# USB_OTG_HS_PHY.net
KiCad netlist of a schematic drawn in Altium Designer
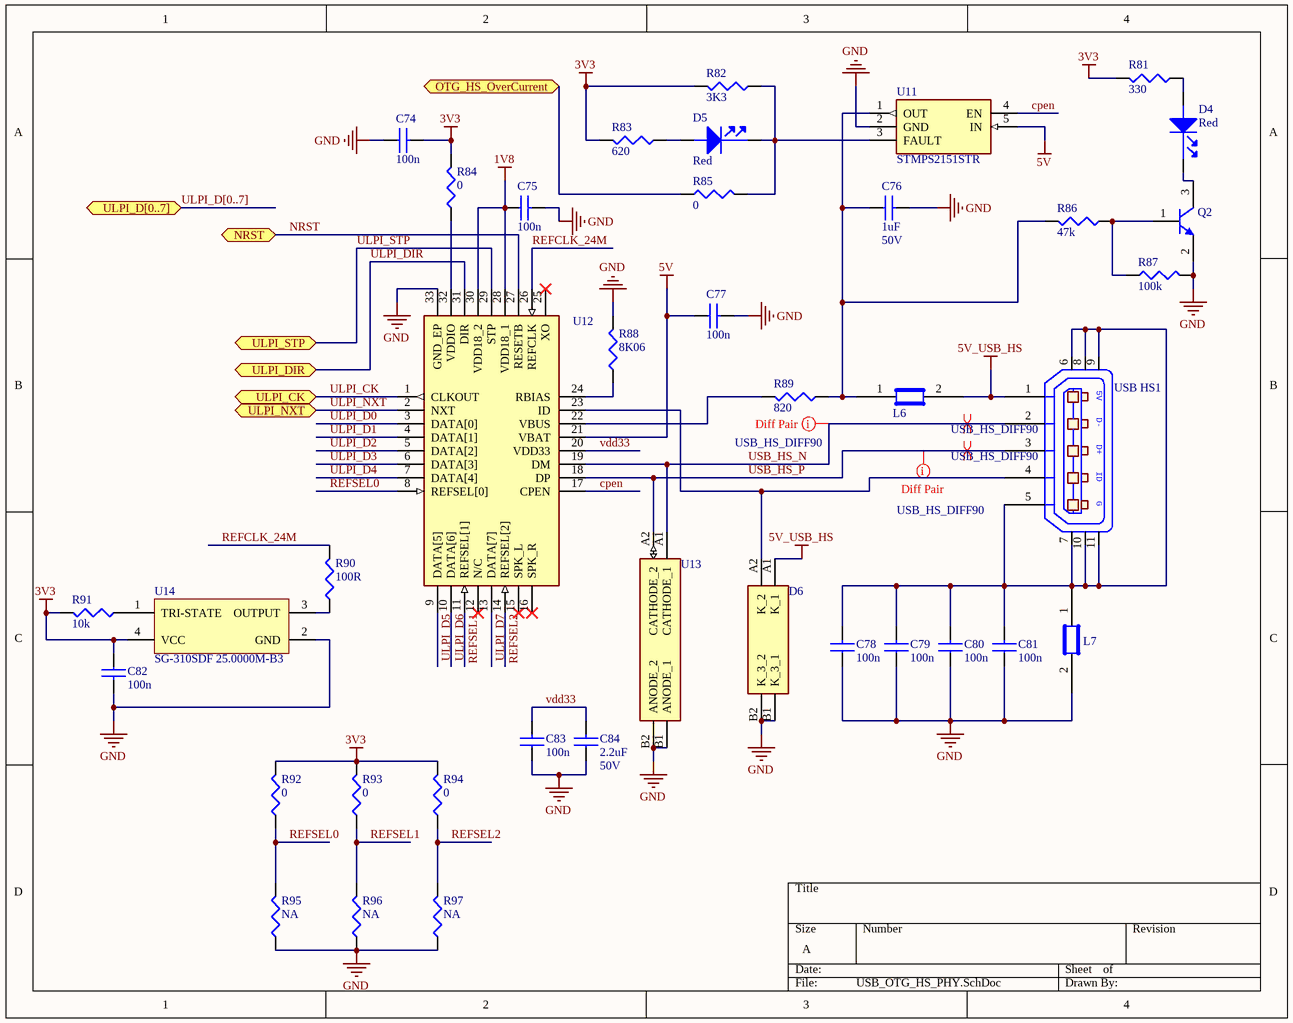
[diagram p0: USB_OTG_HS_PHY.SchDoc]

(export (version "E")
  (design (tool "Eeschema 10.0.6"))
  (components
    (comp (ref "C74")
      (value "100n")
      (footprint "C0402")
      (description "CAP CER .10UF 50V X5R 10% 0402")
      (fields
        (field (name "MANUFACTURER") "TDK Corporation")
        (field (name "MANUFACTURER PART NUMBER") "C1005X5R1H104K")
      )
      (libsource (lib "iMX6_Rex_Development_Baseboard_V1I1") (part "C1005X5R1H104K"))
    )
    (comp (ref "C75")
      (value "100n")
      (footprint "C0402")
      (description "CAP CER .10UF 50V X5R 10% 0402")
      (fields
        (field (name "MANUFACTURER") "TDK Corporation")
        (field (name "MANUFACTURER PART NUMBER") "C1005X5R1H104K")
      )
      (libsource (lib "iMX6_Rex_Development_Baseboard_V1I1") (part "C1005X5R1H104K"))
    )
    (comp (ref "C76")
      (value "1uF")
      (footprint "C0805")
      (description "CAP CER 1UF 50V X7R 0805")
      (fields
        (field (name "MANUFACTURER") "Murata Electronics North America")
        (field (name "MANUFACTURER PART NUMBER") "GRM21BR71H105KA12L")
        (field (name "VOLTAGE - RATED") "50V")
      )
      (libsource (lib "iMX6_Rex_Development_Baseboard_V1I1") (part "GRM21BR71H105KA12L"))
    )
    (comp (ref "C77")
      (value "100n")
      (footprint "C0402")
      (description "CAP CER .10UF 50V X5R 10% 0402")
      (fields
        (field (name "MANUFACTURER") "TDK Corporation")
        (field (name "MANUFACTURER PART NUMBER") "C1005X5R1H104K")
      )
      (libsource (lib "iMX6_Rex_Development_Baseboard_V1I1") (part "C1005X5R1H104K"))
    )
    (comp (ref "C78")
      (value "100n")
      (footprint "C0402")
      (description "CAP CER .10UF 50V X5R 10% 0402")
      (fields
        (field (name "MANUFACTURER") "TDK Corporation")
        (field (name "MANUFACTURER PART NUMBER") "C1005X5R1H104K")
      )
      (libsource (lib "iMX6_Rex_Development_Baseboard_V1I1") (part "C1005X5R1H104K"))
    )
    (comp (ref "C79")
      (value "100n")
      (footprint "C0402")
      (description "CAP CER .10UF 50V X5R 10% 0402")
      (fields
        (field (name "MANUFACTURER") "TDK Corporation")
        (field (name "MANUFACTURER PART NUMBER") "C1005X5R1H104K")
      )
      (libsource (lib "iMX6_Rex_Development_Baseboard_V1I1") (part "C1005X5R1H104K"))
    )
    (comp (ref "C80")
      (value "100n")
      (footprint "C0402")
      (description "CAP CER .10UF 50V X5R 10% 0402")
      (fields
        (field (name "MANUFACTURER") "TDK Corporation")
        (field (name "MANUFACTURER PART NUMBER") "C1005X5R1H104K")
      )
      (libsource (lib "iMX6_Rex_Development_Baseboard_V1I1") (part "C1005X5R1H104K"))
    )
    (comp (ref "C81")
      (value "100n")
      (footprint "C0402")
      (description "CAP CER .10UF 50V X5R 10% 0402")
      (fields
        (field (name "MANUFACTURER") "TDK Corporation")
        (field (name "MANUFACTURER PART NUMBER") "C1005X5R1H104K")
      )
      (libsource (lib "iMX6_Rex_Development_Baseboard_V1I1") (part "C1005X5R1H104K"))
    )
    (comp (ref "C82")
      (value "100n")
      (footprint "C0402")
      (description "CAP CER .10UF 50V X5R 10% 0402")
      (fields
        (field (name "MANUFACTURER") "TDK Corporation")
        (field (name "MANUFACTURER PART NUMBER") "C1005X5R1H104K")
      )
      (libsource (lib "iMX6_Rex_Development_Baseboard_V1I1") (part "C1005X5R1H104K"))
    )
    (comp (ref "C83")
      (value "100n")
      (footprint "C0402")
      (description "CAP CER .10UF 50V X5R 10% 0402")
      (fields
        (field (name "MANUFACTURER") "TDK Corporation")
        (field (name "MANUFACTURER PART NUMBER") "C1005X5R1H104K")
      )
      (libsource (lib "iMX6_Rex_Development_Baseboard_V1I1") (part "C1005X5R1H104K"))
    )
    (comp (ref "C84")
      (value "2.2uF")
      (footprint "C0805")
      (description "CAP CER 1UF 50V X7R 0805")
      (fields
        (field (name "MANUFACTURER") "Murata Electronics North America")
        (field (name "MANUFACTURER PART NUMBER") "GRM21BR71H105KA12L")
        (field (name "VOLTAGE - RATED") "50V")
      )
      (libsource (lib "iMX6_Rex_Development_Baseboard_V1I1") (part "GRM21BR71H105KA12L"))
    )
    (comp (ref "D4")
      (value "Red")
      (footprint "LED_0603")
      (description "LED SMARTLED RED 630NM 0603 SMD")
      (fields
        (field (name "MANUFACTURER") "OSRAM Opto Semiconductors Inc")
        (field (name "MANUFACTURER PART NUMBER") "LS L29K-H1J2-1-Z")
        (field (name ".CHECKED PCB") "RF")
        (field (name ".CHECKED SCH") "RF")
      )
      (libsource (lib "iMX6_Rex_Development_Baseboard_V1I1") (part "LS L29K-H1J2-1-Z"))
    )
    (comp (ref "D5")
      (value "Red")
      (footprint "LED_0603")
      (description "LED SMARTLED RED 630NM 0603 SMD")
      (fields
        (field (name "MANUFACTURER") "OSRAM Opto Semiconductors Inc")
        (field (name "MANUFACTURER PART NUMBER") "LS L29K-H1J2-1-Z")
        (field (name ".CHECKED PCB") "RF")
        (field (name ".CHECKED SCH") "RF")
      )
      (libsource (lib "iMX6_Rex_Development_Baseboard_V1I1") (part "LS L29K-H1J2-1-Z"))
    )
    (comp (ref "D6")
      (value "ESDA14V2-2BF3")
      (footprint "SamacSys:BGA4C40P2X2_77X77X66")
      (description "TVS Diode (Bi-directional)")
      (fields (field (name "MOUSER PART NUMBER") "511-ESDA14V2-2BF3"))
      (libsource (lib "*") (part "ESDA14V2-2BF3"))
    )
    (comp (ref "L6")
      (value "MPZ1608S601A 600OHM/1A")
      (footprint "C0603")
      (description "FERRITE CHIP BEAD 600 OHM SMD 1A")
      (fields
        (field (name "MANUFACTURER") "TDK Corporation")
        (field (name "MANUFACTURER PART NUMBER") "MPZ1608S601A")
        (field (name ".CHECKED PCB") "RF")
        (field (name ".CHECKED SCH") "RF")
      )
      (libsource (lib "iMX6_Rex_Development_Baseboard_V1I1") (part "MPZ1608S601A"))
    )
    (comp (ref "L7")
      (value "MPZ1608S601A 600OHM/1A")
      (footprint "C0603")
      (description "FERRITE CHIP BEAD 600 OHM SMD 1A")
      (fields
        (field (name "MANUFACTURER") "TDK Corporation")
        (field (name "MANUFACTURER PART NUMBER") "MPZ1608S601A")
        (field (name ".CHECKED PCB") "RF")
        (field (name ".CHECKED SCH") "RF")
      )
      (libsource (lib "iMX6_Rex_Development_Baseboard_V1I1") (part "MPZ1608S601A"))
    )
    (comp (ref "Q2")
      (value "MMBT2222A-7-F")
      (footprint "DIOD-SOT23-3_V")
      (description "NPN Small Signal Transistor, 40 V, -55 to 150 degC, 3-Pin SOT23, RoHS, Tape and Reel")
      (fields (field (name "MANUFACTURER") "Diodes Inc"))
      (libsource (lib "MiniPC") (part "CMP-1693-00003-1"))
    )
    (comp (ref "R81")
      (value "330")
      (footprint "R0402")
      (description "RES 10.0K OHM 1/16W 1% 0402 SMD")
      (fields
        (field (name "MANUFACTURER") "Yageo")
        (field (name "MANUFACTURER PART NUMBER") "RC0402FR-0710KL")
      )
      (libsource (lib "iMX6_Rex_Development_Baseboard_V1I1") (part "RC0402FR-0710KL"))
    )
    (comp (ref "R82")
      (value "3K3")
      (footprint "R0402")
      (description "RES 10.0K OHM 1/16W 1% 0402 SMD")
      (fields
        (field (name "MANUFACTURER") "Yageo")
        (field (name "MANUFACTURER PART NUMBER") "RC0402FR-0710KL")
      )
      (libsource (lib "iMX6_Rex_Development_Baseboard_V1I1") (part "RC0402FR-0710KL"))
    )
    (comp (ref "R83")
      (value "620")
      (footprint "R0402")
      (description "RES 10.0K OHM 1/16W 1% 0402 SMD")
      (fields
        (field (name "MANUFACTURER") "Yageo")
        (field (name "MANUFACTURER PART NUMBER") "RC0402FR-0710KL")
      )
      (libsource (lib "iMX6_Rex_Development_Baseboard_V1I1") (part "RC0402FR-0710KL"))
    )
    (comp (ref "R84")
      (value "0")
      (footprint "R0402")
      (description "RES 100 OHM 1/16W 1% 0402 SMD")
      (fields
        (field (name "MANUFACTURER") "Yageo")
        (field (name "MANUFACTURER PART NUMBER") "RC0402FR-07100RL")
        (field (name ".CHECKED PCB") "RF")
        (field (name ".CHECKED SCH") "RF")
      )
      (libsource (lib "iMX6_Rex_Development_Baseboard_V1I1") (part "RC0402FR-07100RL"))
    )
    (comp (ref "R85")
      (value "0")
      (footprint "R0402")
      (description "RES 100 OHM 1/16W 1% 0402 SMD")
      (fields
        (field (name "MANUFACTURER") "Yageo")
        (field (name "MANUFACTURER PART NUMBER") "RC0402FR-07100RL")
        (field (name ".CHECKED PCB") "RF")
        (field (name ".CHECKED SCH") "RF")
      )
      (libsource (lib "iMX6_Rex_Development_Baseboard_V1I1") (part "RC0402FR-07100RL"))
    )
    (comp (ref "R86")
      (value "47k")
      (footprint "R0402")
      (description "RES 10.0K OHM 1/16W 1% 0402 SMD")
      (fields
        (field (name "MANUFACTURER") "Yageo")
        (field (name "MANUFACTURER PART NUMBER") "RC0402FR-0710KL")
      )
      (libsource (lib "iMX6_Rex_Development_Baseboard_V1I1") (part "RC0402FR-0710KL"))
    )
    (comp (ref "R87")
      (value "100k")
      (footprint "R0402")
      (description "RES 100K OHM 1/16W 1% 0402 SMD")
      (fields
        (field (name "MANUFACTURER") "Stackpole Electronics Inc")
        (field (name "MANUFACTURER PART NUMBER") "RMCF0402FT100K")
      )
      (libsource (lib "iMX6_Rex_Development_Baseboard_V1I1") (part "RMCF0402FT100K"))
    )
    (comp (ref "R88")
      (value "8K06")
      (footprint "R0402")
      (description "RES 10.0K OHM 1/16W 1% 0402 SMD")
      (fields
        (field (name "MANUFACTURER") "Yageo")
        (field (name "MANUFACTURER PART NUMBER") "RC0402FR-0710KL")
      )
      (libsource (lib "iMX6_Rex_Development_Baseboard_V1I1") (part "RC0402FR-0710KL"))
    )
    (comp (ref "R89")
      (value "820")
      (footprint "R0402")
      (description "RES 10.0K OHM 1/16W 1% 0402 SMD")
      (fields
        (field (name "MANUFACTURER") "Yageo")
        (field (name "MANUFACTURER PART NUMBER") "RC0402FR-0710KL")
      )
      (libsource (lib "iMX6_Rex_Development_Baseboard_V1I1") (part "RC0402FR-0710KL"))
    )
    (comp (ref "R90")
      (value "100R")
      (footprint "R0402")
      (description "RES 100 OHM 1/16W 1% 0402 SMD")
      (fields
        (field (name "MANUFACTURER") "Yageo")
        (field (name "MANUFACTURER PART NUMBER") "RC0402FR-07100RL")
        (field (name ".CHECKED PCB") "RF")
        (field (name ".CHECKED SCH") "RF")
      )
      (libsource (lib "iMX6_Rex_Development_Baseboard_V1I1") (part "RC0402FR-07100RL"))
    )
    (comp (ref "R91")
      (value "10k")
      (footprint "R0402")
      (description "RES 10.0K OHM 1/16W 1% 0402 SMD")
      (fields
        (field (name "MANUFACTURER") "Yageo")
        (field (name "MANUFACTURER PART NUMBER") "RC0402FR-0710KL")
      )
      (libsource (lib "iMX6_Rex_Development_Baseboard_V1I1") (part "RC0402FR-0710KL"))
    )
    (comp (ref "R92")
      (value "0")
      (footprint "R0402")
      (description "RES 100 OHM 1/16W 1% 0402 SMD")
      (fields
        (field (name "MANUFACTURER") "Yageo")
        (field (name "MANUFACTURER PART NUMBER") "RC0402FR-07100RL")
        (field (name ".CHECKED PCB") "RF")
        (field (name ".CHECKED SCH") "RF")
      )
      (libsource (lib "iMX6_Rex_Development_Baseboard_V1I1") (part "RC0402FR-07100RL"))
    )
    (comp (ref "R93")
      (value "0")
      (footprint "R0402")
      (description "RES 100 OHM 1/16W 1% 0402 SMD")
      (fields
        (field (name "MANUFACTURER") "Yageo")
        (field (name "MANUFACTURER PART NUMBER") "RC0402FR-07100RL")
        (field (name ".CHECKED PCB") "RF")
        (field (name ".CHECKED SCH") "RF")
      )
      (libsource (lib "iMX6_Rex_Development_Baseboard_V1I1") (part "RC0402FR-07100RL"))
    )
    (comp (ref "R94")
      (value "0")
      (footprint "R0402")
      (description "RES 100 OHM 1/16W 1% 0402 SMD")
      (fields
        (field (name "MANUFACTURER") "Yageo")
        (field (name "MANUFACTURER PART NUMBER") "RC0402FR-07100RL")
        (field (name ".CHECKED PCB") "RF")
        (field (name ".CHECKED SCH") "RF")
      )
      (libsource (lib "iMX6_Rex_Development_Baseboard_V1I1") (part "RC0402FR-07100RL"))
    )
    (comp (ref "R95")
      (value "NA")
      (footprint "R0402")
      (description "RES 100 OHM 1/16W 1% 0402 SMD")
      (fields
        (field (name "MANUFACTURER") "Yageo")
        (field (name "MANUFACTURER PART NUMBER") "RC0402FR-07100RL")
        (field (name ".CHECKED PCB") "RF")
        (field (name ".CHECKED SCH") "RF")
      )
      (libsource (lib "iMX6_Rex_Development_Baseboard_V1I1") (part "RC0402FR-07100RL"))
    )
    (comp (ref "R96")
      (value "NA")
      (footprint "R0402")
      (description "RES 100 OHM 1/16W 1% 0402 SMD")
      (fields
        (field (name "MANUFACTURER") "Yageo")
        (field (name "MANUFACTURER PART NUMBER") "RC0402FR-07100RL")
        (field (name ".CHECKED PCB") "RF")
        (field (name ".CHECKED SCH") "RF")
      )
      (libsource (lib "iMX6_Rex_Development_Baseboard_V1I1") (part "RC0402FR-07100RL"))
    )
    (comp (ref "R97")
      (value "NA")
      (footprint "R0402")
      (description "RES 100 OHM 1/16W 1% 0402 SMD")
      (fields
        (field (name "MANUFACTURER") "Yageo")
        (field (name "MANUFACTURER PART NUMBER") "RC0402FR-07100RL")
        (field (name ".CHECKED PCB") "RF")
        (field (name ".CHECKED SCH") "RF")
      )
      (libsource (lib "iMX6_Rex_Development_Baseboard_V1I1") (part "RC0402FR-07100RL"))
    )
    (comp (ref "U11")
      (value "STMPS2151STR")
      (footprint "SamacSys:SOT95P280X145-5N")
      (description "Integrated Circuit")
      (fields
        (field (name "MOUSER PART NUMBER") "511-STMPS2151STR")
        (field (name "RS PART NUMBER") "8805415P")
      )
      (libsource (lib "*") (part "STMPS2151STR"))
    )
    (comp (ref "U12")
      (value "USB3320C-EZK-TR")
      (footprint "SamacSys:QFN50P500X500X100-33N-D")
      (description "Integrated Circuit")
      (fields
        (field (name "MOUSER PART NUMBER") "886-USB3320C-EZK-TR")
        (field (name "RS PART NUMBER") "8246295P")
      )
      (libsource (lib "*") (part "USB3320C-EZK-TR"))
    )
    (comp (ref "U13")
      (value "USBULC6-2F3")
      (footprint "SamacSys:BGA4C40P2X2_82X82X66")
      (description "Integrated Circuit")
      (fields (field (name "MOUSER PART NUMBER") "511-USBULC6-2F3"))
      (libsource (lib "*") (part "USBULC6-2F3"))
    )
    (comp (ref "U14")
      (value "SG-310SDF 25.0000M-B3")
      (footprint "EPSON-SG-310-4_V")
      (description "Crystal Oscillator (SPXO), 2.5 V, 25 MHz, -20 to 70 degC, 4-Pin SMD, RoHS, Tape and Reel")
      (libsource (lib "MiniPC") (part "CMP-1695-00002-3"))
    )
    (comp (ref "USB HS1")
      (value "USB MICRO AB")
      (footprint "USB_Micro_AB")
      (description "CONN RCPT MICRO USB AB R/A SMD")
      (fields
        (field (name "MANUFACTURER") "Molex Inc")
        (field (name "MANUFACTURER PART NUMBER") "0475890001")
        (field (name ".CREATOR") "MM")
        (field (name ".CHECKED PCB") "MM")
        (field (name ".CHECKED SCH") "MM")
      )
      (libsource (lib "iMX6_Rex_Development_Baseboard_V1I1") (part "0475890001"))
    )
  )
  (nets
    (net (code "1") (name "/NRST") (class "Default")
      (node (ref "U12") (pin "27") (pinfunction "RESETB_27") (pintype "passive"))
    )
    (net (code "2") (name "/OTG_HS_OverCurrent") (class "Default")
      (node (ref "R85") (pin "1") (pinfunction "1_1") (pintype "passive"))
    )
    (net (code "3") (name "/REFCLK_24M") (class "Default")
      (node (ref "R90") (pin "2") (pinfunction "2_2") (pintype "passive"))
      (node (ref "U12") (pin "26") (pinfunction "REFCLK_26") (pintype "input"))
    )
    (net (code "4") (name "/REFSEL0") (class "Default")
      (node (ref "R92") (pin "1") (pinfunction "1_1") (pintype "passive"))
      (node (ref "R95") (pin "2") (pinfunction "2_2") (pintype "passive"))
      (node (ref "U12") (pin "8") (pinfunction "REFSEL[0]_8") (pintype "input"))
    )
    (net (code "5") (name "/REFSEL1") (class "Default")
      (node (ref "R93") (pin "1") (pinfunction "1_1") (pintype "passive"))
      (node (ref "R96") (pin "2") (pinfunction "2_2") (pintype "passive"))
      (node (ref "U12") (pin "11") (pinfunction "REFSEL[1]_11") (pintype "input"))
    )
    (net (code "6") (name "/REFSEL2") (class "Default")
      (node (ref "R94") (pin "1") (pinfunction "1_1") (pintype "passive"))
      (node (ref "R97") (pin "2") (pinfunction "2_2") (pintype "passive"))
      (node (ref "U12") (pin "14") (pinfunction "REFSEL[2]_14") (pintype "input"))
    )
    (net (code "7") (name "/ULPI_CK") (class "Default")
      (node (ref "U12") (pin "1") (pinfunction "CLKOUT_1") (pintype "output"))
    )
    (net (code "8") (name "/ULPI_D0") (class "Default")
      (node (ref "U12") (pin "3") (pinfunction "DATA[0]_3") (pintype "passive"))
    )
    (net (code "9") (name "/ULPI_D1") (class "Default")
      (node (ref "U12") (pin "4") (pinfunction "DATA[1]_4") (pintype "passive"))
    )
    (net (code "10") (name "/ULPI_D2") (class "Default")
      (node (ref "U12") (pin "5") (pinfunction "DATA[2]_5") (pintype "passive"))
    )
    (net (code "11") (name "/ULPI_D3") (class "Default")
      (node (ref "U12") (pin "6") (pinfunction "DATA[3]_6") (pintype "passive"))
    )
    (net (code "12") (name "/ULPI_D4") (class "Default")
      (node (ref "U12") (pin "7") (pinfunction "DATA[4]_7") (pintype "passive"))
    )
    (net (code "13") (name "/ULPI_D5") (class "Default")
      (node (ref "U12") (pin "9") (pinfunction "DATA[5]_9") (pintype "passive"))
    )
    (net (code "14") (name "/ULPI_D6") (class "Default")
      (node (ref "U12") (pin "10") (pinfunction "DATA[6]_10") (pintype "passive"))
    )
    (net (code "15") (name "/ULPI_D7") (class "Default")
      (node (ref "U12") (pin "13") (pinfunction "DATA[7]_13") (pintype "passive"))
    )
    (net (code "16") (name "/ULPI_DIR") (class "Default")
      (node (ref "U12") (pin "31") (pinfunction "DIR_31") (pintype "passive"))
    )
    (net (code "18") (name "/ULPI_NXT") (class "Default")
      (node (ref "U12") (pin "2") (pinfunction "NXT_2") (pintype "passive"))
    )
    (net (code "19") (name "/ULPI_STP") (class "Default")
      (node (ref "U12") (pin "29") (pinfunction "STP_29") (pintype "passive"))
    )
    (net (code "20") (name "/USB_HS_N") (class "Default")
      (node (ref "U12") (pin "19") (pinfunction "DM_19") (pintype "passive"))
      (node (ref "U13") (pin "A1") (pinfunction "CATHODE_1_A1") (pintype "passive"))
      (node (ref "USB HS1") (pin "2") (pinfunction "P2_2") (pintype "passive"))
    )
    (net (code "21") (name "/USB_HS_P") (class "Default")
      (node (ref "U12") (pin "18") (pinfunction "DP_18") (pintype "passive"))
      (node (ref "U13") (pin "A2") (pinfunction "CATHODE_2_A2") (pintype "bidirectional"))
      (node (ref "USB HS1") (pin "3") (pinfunction "P3_3") (pintype "passive"))
    )
    (net (code "22") (name "/cpen") (class "Default")
      (node (ref "U11") (pin "4") (pinfunction "EN_4") (pintype "passive"))
      (node (ref "U12") (pin "17") (pinfunction "CPEN_17") (pintype "passive"))
    )
    (net (code "23") (name "/vdd33") (class "Default")
      (node (ref "C83") (pin "2") (pinfunction "2_2") (pintype "passive"))
      (node (ref "C84") (pin "2") (pinfunction "2_2") (pintype "passive"))
      (node (ref "U12") (pin "20") (pinfunction "VDD33_20") (pintype "power_in"))
    )
    (net (code "24") (name "1V8") (class "Default")
      (node (ref "C75") (pin "1") (pinfunction "1_1") (pintype "passive"))
      (node (ref "U12") (pin "28") (pinfunction "VDD18_1_28") (pintype "power_in"))
      (node (ref "U12") (pin "30") (pinfunction "VDD18_2_30") (pintype "power_in"))
    )
    (net (code "25") (name "3V3") (class "Default")
      (node (ref "C74") (pin "2") (pinfunction "2_2") (pintype "passive"))
      (node (ref "C82") (pin "1") (pinfunction "1_1") (pintype "passive"))
      (node (ref "R81") (pin "2") (pinfunction "2_2") (pintype "passive"))
      (node (ref "R82") (pin "2") (pinfunction "2_2") (pintype "passive"))
      (node (ref "R83") (pin "2") (pinfunction "2_2") (pintype "passive"))
      (node (ref "R84") (pin "2") (pinfunction "2_2") (pintype "passive"))
      (node (ref "R91") (pin "2") (pinfunction "2_2") (pintype "passive"))
      (node (ref "R92") (pin "2") (pinfunction "2_2") (pintype "passive"))
      (node (ref "R93") (pin "2") (pinfunction "2_2") (pintype "passive"))
      (node (ref "R94") (pin "2") (pinfunction "2_2") (pintype "passive"))
      (node (ref "U14") (pin "4") (pinfunction "VCC_4") (pintype "power_in"))
    )
    (net (code "26") (name "5V") (class "Default")
      (node (ref "C77") (pin "1") (pinfunction "1_1") (pintype "passive"))
      (node (ref "U11") (pin "5") (pinfunction "IN_5") (pintype "input"))
      (node (ref "U12") (pin "21") (pinfunction "VBAT_21") (pintype "passive"))
    )
    (net (code "27") (name "5V_USB_HS") (class "Default")
      (node (ref "D6") (pin "A1") (pinfunction "K_1_A1") (pintype "passive"))
      (node (ref "L6") (pin "2") (pinfunction "2_2") (pintype "passive"))
      (node (ref "USB HS1") (pin "1") (pinfunction "P1_1") (pintype "passive"))
    )
    (net (code "28") (name "GND") (class "Default")
      (node (ref "C74") (pin "1") (pinfunction "1_1") (pintype "passive"))
      (node (ref "C75") (pin "2") (pinfunction "2_2") (pintype "passive"))
      (node (ref "C76") (pin "2") (pinfunction "2_2") (pintype "passive"))
      (node (ref "C77") (pin "2") (pinfunction "2_2") (pintype "passive"))
      (node (ref "C78") (pin "1") (pinfunction "1_1") (pintype "passive"))
      (node (ref "C79") (pin "1") (pinfunction "1_1") (pintype "passive"))
      (node (ref "C80") (pin "1") (pinfunction "1_1") (pintype "passive"))
      (node (ref "C81") (pin "1") (pinfunction "1_1") (pintype "passive"))
      (node (ref "C82") (pin "2") (pinfunction "2_2") (pintype "passive"))
      (node (ref "C83") (pin "1") (pinfunction "1_1") (pintype "passive"))
      (node (ref "C84") (pin "1") (pinfunction "1_1") (pintype "passive"))
      (node (ref "D6") (pin "B1") (pinfunction "K_3_1_B1") (pintype "passive"))
      (node (ref "D6") (pin "B2") (pinfunction "K_3_2_B2") (pintype "passive"))
      (node (ref "L7") (pin "2") (pinfunction "2_2") (pintype "passive"))
      (node (ref "Q2") (pin "2") (pinfunction "E_2") (pintype "passive"))
      (node (ref "R87") (pin "2") (pinfunction "2_2") (pintype "passive"))
      (node (ref "R88") (pin "2") (pinfunction "2_2") (pintype "passive"))
      (node (ref "R95") (pin "1") (pinfunction "1_1") (pintype "passive"))
      (node (ref "R96") (pin "1") (pinfunction "1_1") (pintype "passive"))
      (node (ref "R97") (pin "1") (pinfunction "1_1") (pintype "passive"))
      (node (ref "U11") (pin "2") (pinfunction "GND_2") (pintype "power_in"))
      (node (ref "U12") (pin "33") (pinfunction "GND_EP_33") (pintype "power_in"))
      (node (ref "U13") (pin "B1") (pinfunction "ANODE_1_B1") (pintype "passive"))
      (node (ref "U13") (pin "B2") (pinfunction "ANODE_2_B2") (pintype "passive"))
      (node (ref "U14") (pin "2") (pinfunction "GND_2") (pintype "power_in"))
    )
    (net (code "29") (name "Net-(D4-ANODE)") (class "Default")
      (node (ref "D4") (pin "2") (pinfunction "ANODE_2") (pintype "passive"))
      (node (ref "R81") (pin "1") (pinfunction "1_1") (pintype "passive"))
    )
    (net (code "30") (name "Net-(D4-cathode)") (class "Default")
      (node (ref "D4") (pin "1") (pinfunction "cathode_1") (pintype "passive"))
      (node (ref "Q2") (pin "3") (pinfunction "C_3") (pintype "passive"))
    )
    (net (code "31") (name "Net-(D5-ANODE)") (class "Default")
      (node (ref "D5") (pin "2") (pinfunction "ANODE_2") (pintype "passive"))
      (node (ref "R83") (pin "1") (pinfunction "1_1") (pintype "passive"))
    )
    (net (code "32") (name "Net-(D5-cathode)") (class "Default")
      (node (ref "D5") (pin "1") (pinfunction "cathode_1") (pintype "passive"))
      (node (ref "R82") (pin "1") (pinfunction "1_1") (pintype "passive"))
      (node (ref "R85") (pin "2") (pinfunction "2_2") (pintype "passive"))
      (node (ref "U11") (pin "3") (pinfunction "FAULT_3") (pintype "passive"))
    )
    (net (code "33") (name "Net-(D6-K_2)") (class "Default")
      (node (ref "D6") (pin "A2") (pinfunction "K_2_A2") (pintype "passive"))
      (node (ref "U12") (pin "23") (pinfunction "ID_23") (pintype "passive"))
      (node (ref "USB HS1") (pin "4") (pinfunction "P4_4") (pintype "passive"))
    )
    (net (code "34") (name "Net-(Q2-B)") (class "Default")
      (node (ref "Q2") (pin "1") (pinfunction "B_1") (pintype "passive"))
      (node (ref "R86") (pin "1") (pinfunction "1_1") (pintype "passive"))
      (node (ref "R87") (pin "1") (pinfunction "1_1") (pintype "passive"))
    )
    (net (code "35") (name "Net-(U11-OUT)") (class "Default")
      (node (ref "C76") (pin "1") (pinfunction "1_1") (pintype "passive"))
      (node (ref "L6") (pin "1") (pinfunction "1_1") (pintype "passive"))
      (node (ref "R86") (pin "2") (pinfunction "2_2") (pintype "passive"))
      (node (ref "R89") (pin "1") (pinfunction "1_1") (pintype "passive"))
      (node (ref "U11") (pin "1") (pinfunction "OUT_1") (pintype "output"))
    )
    (net (code "36") (name "Net-(U12-RBIAS)") (class "Default")
      (node (ref "R88") (pin "1") (pinfunction "1_1") (pintype "passive"))
      (node (ref "U12") (pin "24") (pinfunction "RBIAS_24") (pintype "passive"))
    )
    (net (code "37") (name "Net-(U12-VBUS)") (class "Default")
      (node (ref "R89") (pin "2") (pinfunction "2_2") (pintype "passive"))
      (node (ref "U12") (pin "22") (pinfunction "VBUS_22") (pintype "passive"))
    )
    (net (code "38") (name "Net-(U12-VDDIO)") (class "Default")
      (node (ref "R84") (pin "1") (pinfunction "1_1") (pintype "passive"))
      (node (ref "U12") (pin "32") (pinfunction "VDDIO_32") (pintype "power_in"))
    )
    (net (code "39") (name "Net-(U14-OUTPUT)") (class "Default")
      (node (ref "R90") (pin "1") (pinfunction "1_1") (pintype "passive"))
      (node (ref "U14") (pin "3") (pinfunction "OUTPUT_3") (pintype "passive"))
    )
    (net (code "40") (name "Net-(U14-TRI-STATE)") (class "Default")
      (node (ref "R91") (pin "1") (pinfunction "1_1") (pintype "passive"))
      (node (ref "U14") (pin "1") (pinfunction "TRI-STATE_1") (pintype "passive"))
    )
    (net (code "41") (name "Net-(USB HS1-P5)") (class "Default")
      (node (ref "C78") (pin "2") (pinfunction "2_2") (pintype "passive"))
      (node (ref "C79") (pin "2") (pinfunction "2_2") (pintype "passive"))
      (node (ref "C80") (pin "2") (pinfunction "2_2") (pintype "passive"))
      (node (ref "C81") (pin "2") (pinfunction "2_2") (pintype "passive"))
      (node (ref "L7") (pin "1") (pinfunction "1_1") (pintype "passive"))
      (node (ref "USB HS1") (pin "10") (pinfunction "10_10") (pintype "passive"))
      (node (ref "USB HS1") (pin "11") (pinfunction "11_11") (pintype "passive"))
      (node (ref "USB HS1") (pin "5") (pinfunction "P5_5") (pintype "passive"))
      (node (ref "USB HS1") (pin "6") (pinfunction "6_6") (pintype "passive"))
      (node (ref "USB HS1") (pin "7") (pinfunction "7_7") (pintype "passive"))
      (node (ref "USB HS1") (pin "8") (pinfunction "8_8") (pintype "passive"))
      (node (ref "USB HS1") (pin "9") (pinfunction "9_9") (pintype "passive"))
    )
    (net (code "42") (name "unconnected-(U12-N{slash}C-Pad12)") (class "Default")
      (node (ref "U12") (pin "12") (pinfunction "N/C_12") (pintype "passive+no_connect"))
    )
    (net (code "43") (name "unconnected-(U12-SPK_L-Pad15)") (class "Default")
      (node (ref "U12") (pin "15") (pinfunction "SPK_L_15") (pintype "passive+no_connect"))
    )
    (net (code "44") (name "unconnected-(U12-SPK_R-Pad16)") (class "Default")
      (node (ref "U12") (pin "16") (pinfunction "SPK_R_16") (pintype "passive+no_connect"))
    )
    (net (code "45") (name "unconnected-(U12-XO-Pad25)") (class "Default")
      (node (ref "U12") (pin "25") (pinfunction "XO_25") (pintype "passive+no_connect"))
    )
  )
)
